# untitled2.net
KiCad netlist of a schematic drawn in EAGLE
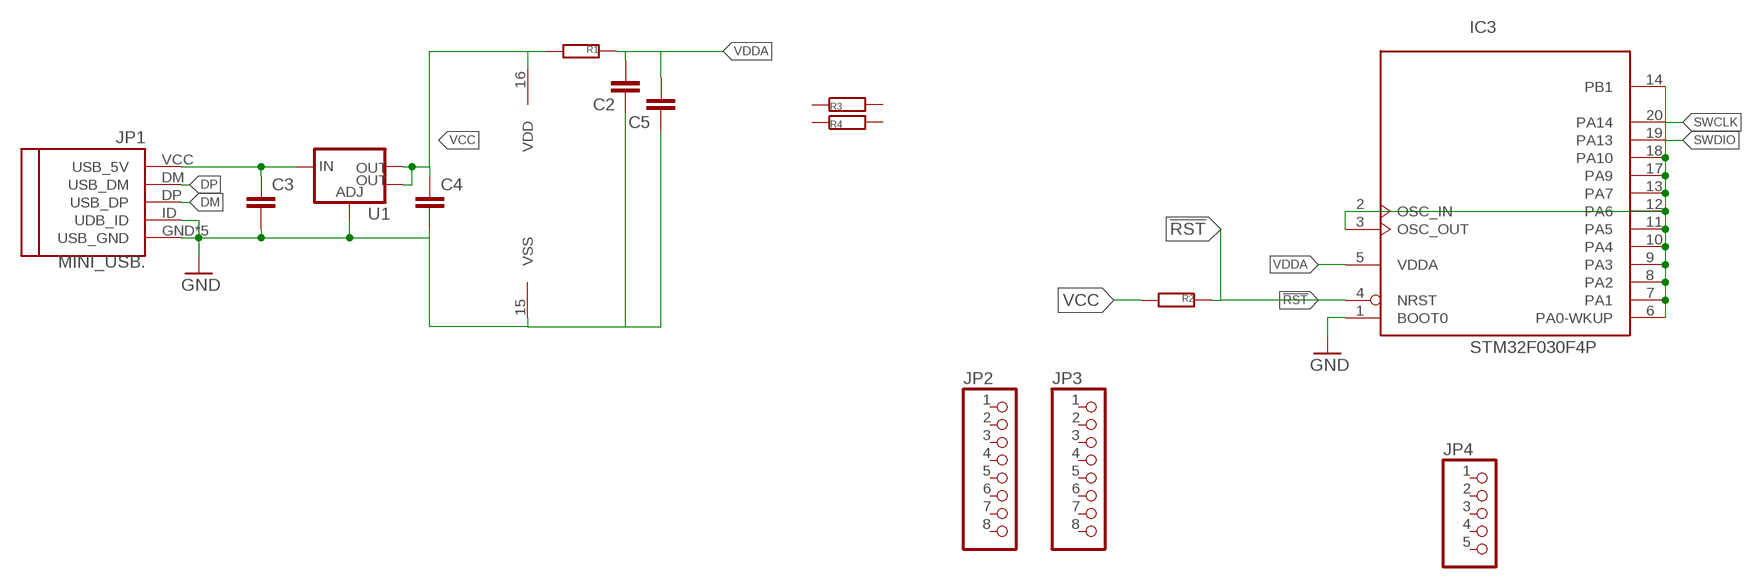
[diagram p0: schematic, sheet 1]

(export (version "E")
  (design (tool "Eeschema 10.0.6"))
  (components
    (comp (ref "C2")
      (value "CC0805")
      (footprint "eagle-import:C0805")
      (libsource (lib "eagle-import") (part "CC0805"))
    )
    (comp (ref "C3")
      (value "CC0805")
      (footprint "eagle-import:C0805")
      (libsource (lib "eagle-import") (part "CC0805"))
    )
    (comp (ref "C4")
      (value "CC0805")
      (footprint "eagle-import:C0805")
      (libsource (lib "eagle-import") (part "CC0805"))
    )
    (comp (ref "C5")
      (value "CC0805")
      (footprint "eagle-import:C0805")
      (libsource (lib "eagle-import") (part "CC0805"))
    )
    (comp (ref "IC3")
      (value "STM32F030F4P")
      (footprint "eagle-import:TSSOP20-I")
      (libsource (lib "eagle-import") (part "STM32F030FP4"))
    )
    (comp (ref "JP1")
      (value "MINI_USB.")
      (footprint "eagle-import:32005-201")
      (libsource (lib "eagle-import") (part "MINI_USB."))
    )
    (comp (ref "JP2")
      (value "PINHD-1X08_2.54")
      (footprint "eagle-import:1X08")
      (libsource (lib "eagle-import") (part "PINHD-1X08_2.54"))
    )
    (comp (ref "JP3")
      (value "PINHD-1X08_2.54")
      (footprint "eagle-import:1X08")
      (libsource (lib "eagle-import") (part "PINHD-1X08_2.54"))
    )
    (comp (ref "JP4")
      (value "PINHD-1X05_2.54")
      (footprint "eagle-import:1X05")
      (libsource (lib "eagle-import") (part "PINHD-1X05_2.54"))
    )
    (comp (ref "R1")
      (value "R0603")
      (footprint "eagle-import:0603")
      (libsource (lib "eagle-import") (part "R0603"))
    )
    (comp (ref "R2")
      (value "R0603")
      (footprint "eagle-import:0603")
      (libsource (lib "eagle-import") (part "R0603"))
    )
    (comp (ref "R3")
      (value "R0805")
      (footprint "eagle-import:R0805")
      (libsource (lib "eagle-import") (part "R0805"))
    )
    (comp (ref "R4")
      (value "R0805")
      (footprint "eagle-import:R0805")
      (libsource (lib "eagle-import") (part "R0805"))
    )
    (comp (ref "U1")
      (value "V_REG_LM1117SOT223")
      (footprint "eagle-import:SOT223")
      (libsource (lib "eagle-import") (part "V_REG_LM1117SOT223"))
    )
  )
  (nets
    (net (code "1") (name "/~{RST}") (class "Default")
      (node (ref "IC3") (pin "4") (pinfunction "NRST_4") (pintype "bidirectional"))
      (node (ref "R2") (pin "1") (pinfunction "1_1") (pintype "passive"))
    )
    (net (code "2") (name "DM") (class "Default")
      (node (ref "JP1") (pin "DP") (pinfunction "USB_DP_DP") (pintype "bidirectional"))
    )
    (net (code "3") (name "DP") (class "Default")
      (node (ref "JP1") (pin "DM") (pinfunction "USB_DM_DM") (pintype "bidirectional"))
    )
    (net (code "4") (name "GND") (class "Default")
      (node (ref "C2") (pin "1") (pinfunction "1_1") (pintype "passive"))
      (node (ref "C3") (pin "2") (pinfunction "2_2") (pintype "passive"))
      (node (ref "C4") (pin "2") (pinfunction "2_2") (pintype "passive"))
      (node (ref "C5") (pin "1") (pinfunction "1_1") (pintype "passive"))
      (node (ref "IC3") (pin "1") (pinfunction "BOOT0_1") (pintype "input"))
      (node (ref "IC3") (pin "15") (pinfunction "VSS_15") (pintype "power_in"))
      (node (ref "JP1") (pin "GND") (pinfunction "USB_GND_GND") (pintype "power_in"))
      (node (ref "JP1") (pin "ID") (pinfunction "UDB_ID_ID") (pintype "bidirectional"))
      (node (ref "JP1") (pin "M1") (pinfunction "USB_GND_M1") (pintype "power_in"))
      (node (ref "JP1") (pin "M2") (pinfunction "USB_GND_M2") (pintype "power_in"))
      (node (ref "JP1") (pin "M3") (pinfunction "USB_GND_M3") (pintype "power_in"))
      (node (ref "JP1") (pin "M4") (pinfunction "USB_GND_M4") (pintype "power_in"))
      (node (ref "U1") (pin "1") (pinfunction "ADJ_1") (pintype "input"))
    )
    (net (code "5") (name "Net-(IC3A-OSC_IN)") (class "Default")
      (node (ref "IC3") (pin "10") (pinfunction "PA4_10") (pintype "bidirectional"))
      (node (ref "IC3") (pin "11") (pinfunction "PA5_11") (pintype "bidirectional"))
      (node (ref "IC3") (pin "12") (pinfunction "PA6_12") (pintype "bidirectional"))
      (node (ref "IC3") (pin "13") (pinfunction "PA7_13") (pintype "bidirectional"))
      (node (ref "IC3") (pin "14") (pinfunction "PB1_14") (pintype "bidirectional"))
      (node (ref "IC3") (pin "17") (pinfunction "PA9_17") (pintype "bidirectional"))
      (node (ref "IC3") (pin "18") (pinfunction "PA10_18") (pintype "bidirectional"))
      (node (ref "IC3") (pin "2") (pinfunction "OSC_IN_2") (pintype "bidirectional"))
      (node (ref "IC3") (pin "3") (pinfunction "OSC_OUT_3") (pintype "bidirectional"))
      (node (ref "IC3") (pin "6") (pinfunction "PA0-WKUP_6") (pintype "bidirectional"))
      (node (ref "IC3") (pin "7") (pinfunction "PA1_7") (pintype "bidirectional"))
      (node (ref "IC3") (pin "8") (pinfunction "PA2_8") (pintype "bidirectional"))
      (node (ref "IC3") (pin "9") (pinfunction "PA3_9") (pintype "bidirectional"))
    )
    (net (code "6") (name "Net-(JP1-USB_5V)") (class "Default")
      (node (ref "C3") (pin "1") (pinfunction "1_1") (pintype "passive"))
      (node (ref "JP1") (pin "VCC") (pinfunction "USB_5V_VCC") (pintype "power_in"))
      (node (ref "U1") (pin "3") (pinfunction "IN_3") (pintype "input"))
    )
    (net (code "7") (name "SWCLK") (class "Default")
      (node (ref "IC3") (pin "20") (pinfunction "PA14_20") (pintype "bidirectional"))
    )
    (net (code "8") (name "SWDIO") (class "Default")
      (node (ref "IC3") (pin "19") (pinfunction "PA13_19") (pintype "bidirectional"))
    )
    (net (code "9") (name "VCC") (class "Default")
      (node (ref "C4") (pin "1") (pinfunction "1_1") (pintype "passive"))
      (node (ref "IC3") (pin "16") (pinfunction "VDD_16") (pintype "power_in"))
      (node (ref "R1") (pin "2") (pinfunction "2_2") (pintype "passive"))
      (node (ref "R2") (pin "2") (pinfunction "2_2") (pintype "passive"))
      (node (ref "U1") (pin "2") (pinfunction "OUT_2") (pintype "output"))
      (node (ref "U1") (pin "4") (pinfunction "OUT_4") (pintype "output"))
    )
    (net (code "10") (name "VDDA") (class "Default")
      (node (ref "C2") (pin "2") (pinfunction "2_2") (pintype "passive"))
      (node (ref "C5") (pin "2") (pinfunction "2_2") (pintype "passive"))
      (node (ref "IC3") (pin "5") (pinfunction "VDDA_5") (pintype "power_in"))
      (node (ref "R1") (pin "1") (pinfunction "1_1") (pintype "passive"))
    )
    (net (code "11") (name "unconnected-(JP2-Pad1)") (class "Default")
      (node (ref "JP2") (pin "1") (pinfunction "1_1") (pintype "passive"))
    )
    (net (code "12") (name "unconnected-(JP2-Pad2)") (class "Default")
      (node (ref "JP2") (pin "2") (pinfunction "2_2") (pintype "passive"))
    )
    (net (code "13") (name "unconnected-(JP2-Pad3)") (class "Default")
      (node (ref "JP2") (pin "3") (pinfunction "3_3") (pintype "passive"))
    )
    (net (code "14") (name "unconnected-(JP2-Pad4)") (class "Default")
      (node (ref "JP2") (pin "4") (pinfunction "4_4") (pintype "passive"))
    )
    (net (code "15") (name "unconnected-(JP2-Pad5)") (class "Default")
      (node (ref "JP2") (pin "5") (pinfunction "5_5") (pintype "passive"))
    )
    (net (code "16") (name "unconnected-(JP2-Pad6)") (class "Default")
      (node (ref "JP2") (pin "6") (pinfunction "6_6") (pintype "passive"))
    )
    (net (code "17") (name "unconnected-(JP2-Pad7)") (class "Default")
      (node (ref "JP2") (pin "7") (pinfunction "7_7") (pintype "passive"))
    )
    (net (code "18") (name "unconnected-(JP2-Pad8)") (class "Default")
      (node (ref "JP2") (pin "8") (pinfunction "8_8") (pintype "passive"))
    )
    (net (code "19") (name "unconnected-(JP3-Pad1)") (class "Default")
      (node (ref "JP3") (pin "1") (pinfunction "1_1") (pintype "passive"))
    )
    (net (code "20") (name "unconnected-(JP3-Pad2)") (class "Default")
      (node (ref "JP3") (pin "2") (pinfunction "2_2") (pintype "passive"))
    )
    (net (code "21") (name "unconnected-(JP3-Pad3)") (class "Default")
      (node (ref "JP3") (pin "3") (pinfunction "3_3") (pintype "passive"))
    )
    (net (code "22") (name "unconnected-(JP3-Pad4)") (class "Default")
      (node (ref "JP3") (pin "4") (pinfunction "4_4") (pintype "passive"))
    )
    (net (code "23") (name "unconnected-(JP3-Pad5)") (class "Default")
      (node (ref "JP3") (pin "5") (pinfunction "5_5") (pintype "passive"))
    )
    (net (code "24") (name "unconnected-(JP3-Pad6)") (class "Default")
      (node (ref "JP3") (pin "6") (pinfunction "6_6") (pintype "passive"))
    )
    (net (code "25") (name "unconnected-(JP3-Pad7)") (class "Default")
      (node (ref "JP3") (pin "7") (pinfunction "7_7") (pintype "passive"))
    )
    (net (code "26") (name "unconnected-(JP3-Pad8)") (class "Default")
      (node (ref "JP3") (pin "8") (pinfunction "8_8") (pintype "passive"))
    )
    (net (code "27") (name "unconnected-(JP4-Pad1)") (class "Default")
      (node (ref "JP4") (pin "1") (pinfunction "1_1") (pintype "passive"))
    )
    (net (code "28") (name "unconnected-(JP4-Pad2)") (class "Default")
      (node (ref "JP4") (pin "2") (pinfunction "2_2") (pintype "passive"))
    )
    (net (code "29") (name "unconnected-(JP4-Pad3)") (class "Default")
      (node (ref "JP4") (pin "3") (pinfunction "3_3") (pintype "passive"))
    )
    (net (code "30") (name "unconnected-(JP4-Pad4)") (class "Default")
      (node (ref "JP4") (pin "4") (pinfunction "4_4") (pintype "passive"))
    )
    (net (code "31") (name "unconnected-(JP4-Pad5)") (class "Default")
      (node (ref "JP4") (pin "5") (pinfunction "5_5") (pintype "passive"))
    )
    (net (code "32") (name "unconnected-(R3-Pad1)") (class "Default")
      (node (ref "R3") (pin "1") (pinfunction "1_1") (pintype "passive"))
    )
    (net (code "33") (name "unconnected-(R3-Pad2)") (class "Default")
      (node (ref "R3") (pin "2") (pinfunction "2_2") (pintype "passive"))
    )
    (net (code "34") (name "unconnected-(R4-Pad1)") (class "Default")
      (node (ref "R4") (pin "1") (pinfunction "1_1") (pintype "passive"))
    )
    (net (code "35") (name "unconnected-(R4-Pad2)") (class "Default")
      (node (ref "R4") (pin "2") (pinfunction "2_2") (pintype "passive"))
    )
  )
)
